# brain.net
KiCad netlist of a schematic drawn in Altium Designer
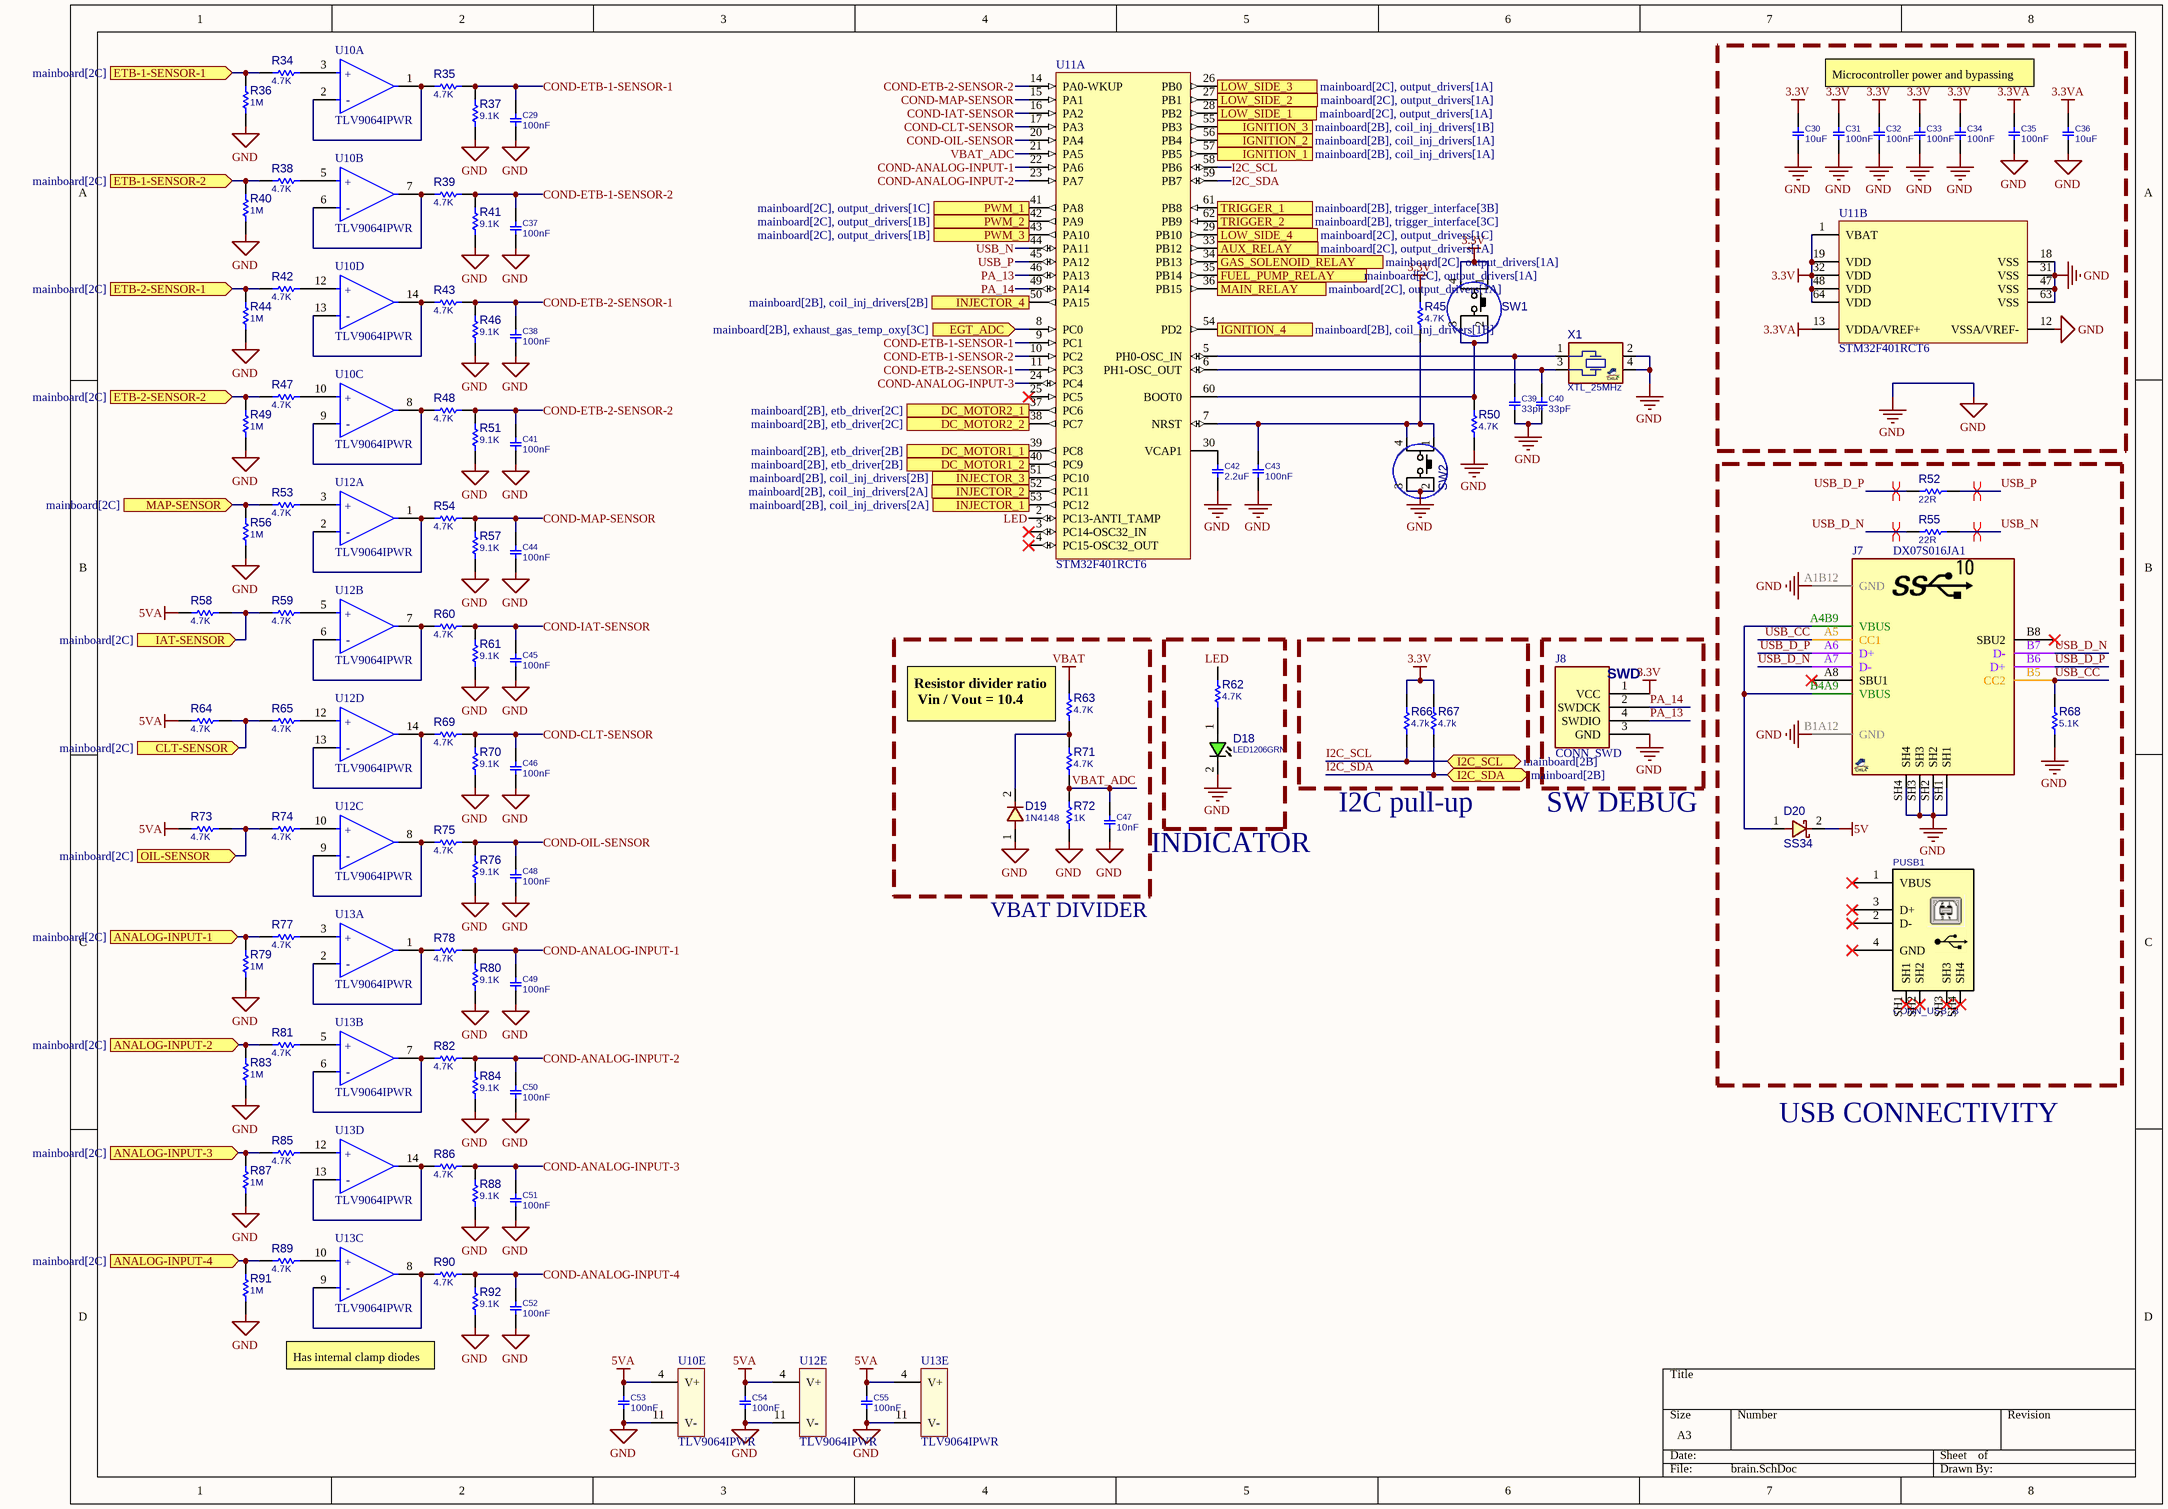
[diagram p0: brain.SchDoc]

(export (version "E")
  (design (tool "Eeschema 10.0.6"))
  (components
    (comp (ref "C29")
      (value "100nF")
      (footprint "C0805")
      (description "CAP, MLCC")
      (fields (field (name "MANF_P#") "MANF_PART#") (field (name "MANF") "Murata"))
      (libsource (lib "passive_smd") (part "CAP_SMD_MLCC"))
    )
    (comp (ref "C30")
      (value "10uF")
      (footprint "C0805")
      (description "CAP, MLCC")
      (fields (field (name "MANF_P#") "MANF_PART#") (field (name "MANF") "Murata"))
      (libsource (lib "passive_smd") (part "CAP_SMD_MLCC"))
    )
    (comp (ref "C31")
      (value "100nF")
      (footprint "C0805")
      (description "CAP, MLCC")
      (fields (field (name "MANF_P#") "MANF_PART#") (field (name "MANF") "Murata"))
      (libsource (lib "passive_smd") (part "CAP_SMD_MLCC"))
    )
    (comp (ref "C32")
      (value "100nF")
      (footprint "C0805")
      (description "CAP, MLCC")
      (fields (field (name "MANF_P#") "MANF_PART#") (field (name "MANF") "Murata"))
      (libsource (lib "passive_smd") (part "CAP_SMD_MLCC"))
    )
    (comp (ref "C33")
      (value "100nF")
      (footprint "C0805")
      (description "CAP, MLCC")
      (fields (field (name "MANF_P#") "MANF_PART#") (field (name "MANF") "Murata"))
      (libsource (lib "passive_smd") (part "CAP_SMD_MLCC"))
    )
    (comp (ref "C34")
      (value "100nF")
      (footprint "C0805")
      (description "CAP, MLCC")
      (fields (field (name "MANF_P#") "MANF_PART#") (field (name "MANF") "Murata"))
      (libsource (lib "passive_smd") (part "CAP_SMD_MLCC"))
    )
    (comp (ref "C35")
      (value "100nF")
      (footprint "C0805")
      (description "CAP, MLCC")
      (fields (field (name "MANF_P#") "MANF_PART#") (field (name "MANF") "Murata"))
      (libsource (lib "passive_smd") (part "CAP_SMD_MLCC"))
    )
    (comp (ref "C36")
      (value "10uF")
      (footprint "C0805")
      (description "CAP, MLCC")
      (fields (field (name "MANF_P#") "MANF_PART#") (field (name "MANF") "Murata"))
      (libsource (lib "passive_smd") (part "CAP_SMD_MLCC"))
    )
    (comp (ref "C37")
      (value "100nF")
      (footprint "C0805")
      (description "CAP, MLCC")
      (fields (field (name "MANF_P#") "MANF_PART#") (field (name "MANF") "Murata"))
      (libsource (lib "passive_smd") (part "CAP_SMD_MLCC"))
    )
    (comp (ref "C38")
      (value "100nF")
      (footprint "C0805")
      (description "CAP, MLCC")
      (fields (field (name "MANF_P#") "MANF_PART#") (field (name "MANF") "Murata"))
      (libsource (lib "passive_smd") (part "CAP_SMD_MLCC"))
    )
    (comp (ref "C39")
      (value "33pF")
      (footprint "C0805")
      (description "CAP, MLCC")
      (fields (field (name "MANF_P#") "MANF_PART#") (field (name "MANF") "Murata"))
      (libsource (lib "passive_smd") (part "CAP_SMD_MLCC"))
    )
    (comp (ref "C40")
      (value "33pF")
      (footprint "C0805")
      (description "CAP, MLCC")
      (fields (field (name "MANF_P#") "MANF_PART#") (field (name "MANF") "Murata"))
      (libsource (lib "passive_smd") (part "CAP_SMD_MLCC"))
    )
    (comp (ref "C41")
      (value "100nF")
      (footprint "C0805")
      (description "CAP, MLCC")
      (fields (field (name "MANF_P#") "MANF_PART#") (field (name "MANF") "Murata"))
      (libsource (lib "passive_smd") (part "CAP_SMD_MLCC"))
    )
    (comp (ref "C42")
      (value "2.2uF")
      (footprint "C0805")
      (description "CAP, MLCC")
      (fields (field (name "MANF_P#") "MANF_PART#") (field (name "MANF") "Murata"))
      (libsource (lib "passive_smd") (part "CAP_SMD_MLCC"))
    )
    (comp (ref "C43")
      (value "100nF")
      (footprint "C0805")
      (description "CAP, MLCC")
      (fields (field (name "MANF_P#") "MANF_PART#") (field (name "MANF") "Murata"))
      (libsource (lib "passive_smd") (part "CAP_SMD_MLCC"))
    )
    (comp (ref "C44")
      (value "100nF")
      (footprint "C0805")
      (description "CAP, MLCC")
      (fields (field (name "MANF_P#") "MANF_PART#") (field (name "MANF") "Murata"))
      (libsource (lib "passive_smd") (part "CAP_SMD_MLCC"))
    )
    (comp (ref "C45")
      (value "100nF")
      (footprint "C0805")
      (description "CAP, MLCC")
      (fields (field (name "MANF_P#") "MANF_PART#") (field (name "MANF") "Murata"))
      (libsource (lib "passive_smd") (part "CAP_SMD_MLCC"))
    )
    (comp (ref "C46")
      (value "100nF")
      (footprint "C0805")
      (description "CAP, MLCC")
      (fields (field (name "MANF_P#") "MANF_PART#") (field (name "MANF") "Murata"))
      (libsource (lib "passive_smd") (part "CAP_SMD_MLCC"))
    )
    (comp (ref "C47")
      (value "10nF")
      (footprint "C0805")
      (description "CAP, MLCC")
      (fields (field (name "MANF_P#") "MANF_PART#") (field (name "MANF") "Murata"))
      (libsource (lib "passive_smd") (part "CAP_SMD_MLCC"))
    )
    (comp (ref "C48")
      (value "100nF")
      (footprint "C0805")
      (description "CAP, MLCC")
      (fields (field (name "MANF_P#") "MANF_PART#") (field (name "MANF") "Murata"))
      (libsource (lib "passive_smd") (part "CAP_SMD_MLCC"))
    )
    (comp (ref "C49")
      (value "100nF")
      (footprint "C0805")
      (description "CAP, MLCC")
      (fields (field (name "MANF_P#") "MANF_PART#") (field (name "MANF") "Murata"))
      (libsource (lib "passive_smd") (part "CAP_SMD_MLCC"))
    )
    (comp (ref "C50")
      (value "100nF")
      (footprint "C0805")
      (description "CAP, MLCC")
      (fields (field (name "MANF_P#") "MANF_PART#") (field (name "MANF") "Murata"))
      (libsource (lib "passive_smd") (part "CAP_SMD_MLCC"))
    )
    (comp (ref "C51")
      (value "100nF")
      (footprint "C0805")
      (description "CAP, MLCC")
      (fields (field (name "MANF_P#") "MANF_PART#") (field (name "MANF") "Murata"))
      (libsource (lib "passive_smd") (part "CAP_SMD_MLCC"))
    )
    (comp (ref "C52")
      (value "100nF")
      (footprint "C0805")
      (description "CAP, MLCC")
      (fields (field (name "MANF_P#") "MANF_PART#") (field (name "MANF") "Murata"))
      (libsource (lib "passive_smd") (part "CAP_SMD_MLCC"))
    )
    (comp (ref "C53")
      (value "100nF")
      (footprint "C0805")
      (description "CAP, MLCC")
      (fields (field (name "MANF_P#") "MANF_PART#") (field (name "MANF") "Murata"))
      (libsource (lib "passive_smd") (part "CAP_SMD_MLCC"))
    )
    (comp (ref "C54")
      (value "100nF")
      (footprint "C0805")
      (description "CAP, MLCC")
      (fields (field (name "MANF_P#") "MANF_PART#") (field (name "MANF") "Murata"))
      (libsource (lib "passive_smd") (part "CAP_SMD_MLCC"))
    )
    (comp (ref "C55")
      (value "100nF")
      (footprint "C0805")
      (description "CAP, MLCC")
      (fields (field (name "MANF_P#") "MANF_PART#") (field (name "MANF") "Murata"))
      (libsource (lib "passive_smd") (part "CAP_SMD_MLCC"))
    )
    (comp (ref "D18")
      (value "LED1206GRN")
      (footprint "LED1206GRN")
      (description "LED, SMD, 1206, GREEN")
      (libsource (lib "led(diode)") (part "LED_SMD_1206_GRN"))
    )
    (comp (ref "D19")
      (value "1N4148")
      (footprint "D_SOD80")
      (description "DIODE, FAST SWTICHING, 0.3A, 0.5W")
      (fields (field (name "MANF") "MANF"))
      (libsource (lib "diode") (part "DIODE_SMD_1N4148_SOD80"))
    )
    (comp (ref "D20")
      (value "SS34")
      (footprint "D_SMB")
      (description "DIODE, SCHOTTKY, 20V, 3A")
      (fields (field (name "MANF") "VISHAY"))
      (libsource (lib "diode") (part "DIODE_SMD_SCHOTTKY_SS34"))
    )
    (comp (ref "J7")
      (value "DX07S016JA1")
      (footprint "USBC_SMD_16_DX07S016JA1")
      (description "CONN, USB, Type C, USB 2.0, Right-Angle, SMD")
      (fields (field (name "MANF") "JAE") (field (name "MANF_P#") "DX07S016JA1R1500"))
      (libsource (lib "conn_usbc") (part "CONN_USBC_SMD_16_DX07S016JA1"))
    )
    (comp (ref "J8")
      (value "CONN_SWD")
      (footprint "WF_4")
      (description "CONN, SWD, ST")
      (libsource (lib "conn_program") (part "CONN_SWD"))
    )
    (comp (ref "PUSB1")
      (value "CONN_USB_B")
      (footprint "USB_B_ST")
      (description "CONN, USB, B, STRAIGHT, THD")
      (libsource (lib "conn_usb") (part "CONN_USB_B_ST"))
    )
    (comp (ref "R34")
      (value "4.7K")
      (footprint "R0805")
      (description "RESISTOR, SMD")
      (libsource (lib "passive_smd") (part "RES_SMD"))
    )
    (comp (ref "R35")
      (value "4.7K")
      (footprint "R0805")
      (description "RESISTOR, SMD")
      (libsource (lib "passive_smd") (part "RES_SMD"))
    )
    (comp (ref "R36")
      (value "1M")
      (footprint "R0805")
      (description "RESISTOR, SMD")
      (libsource (lib "passive_smd") (part "RES_SMD"))
    )
    (comp (ref "R37")
      (value "9.1K")
      (footprint "R0805")
      (description "RESISTOR, SMD")
      (libsource (lib "passive_smd") (part "RES_SMD"))
    )
    (comp (ref "R38")
      (value "4.7K")
      (footprint "R0805")
      (description "RESISTOR, SMD")
      (libsource (lib "passive_smd") (part "RES_SMD"))
    )
    (comp (ref "R39")
      (value "4.7K")
      (footprint "R0805")
      (description "RESISTOR, SMD")
      (libsource (lib "passive_smd") (part "RES_SMD"))
    )
    (comp (ref "R40")
      (value "1M")
      (footprint "R0805")
      (description "RESISTOR, SMD")
      (libsource (lib "passive_smd") (part "RES_SMD"))
    )
    (comp (ref "R41")
      (value "9.1K")
      (footprint "R0805")
      (description "RESISTOR, SMD")
      (libsource (lib "passive_smd") (part "RES_SMD"))
    )
    (comp (ref "R42")
      (value "4.7K")
      (footprint "R0805")
      (description "RESISTOR, SMD")
      (libsource (lib "passive_smd") (part "RES_SMD"))
    )
    (comp (ref "R43")
      (value "4.7K")
      (footprint "R0805")
      (description "RESISTOR, SMD")
      (libsource (lib "passive_smd") (part "RES_SMD"))
    )
    (comp (ref "R44")
      (value "1M")
      (footprint "R0805")
      (description "RESISTOR, SMD")
      (libsource (lib "passive_smd") (part "RES_SMD"))
    )
    (comp (ref "R45")
      (value "4.7K")
      (footprint "R0805")
      (description "RESISTOR, SMD")
      (libsource (lib "passive_smd") (part "RES_SMD"))
    )
    (comp (ref "R46")
      (value "9.1K")
      (footprint "R0805")
      (description "RESISTOR, SMD")
      (libsource (lib "passive_smd") (part "RES_SMD"))
    )
    (comp (ref "R47")
      (value "4.7K")
      (footprint "R0805")
      (description "RESISTOR, SMD")
      (libsource (lib "passive_smd") (part "RES_SMD"))
    )
    (comp (ref "R48")
      (value "4.7K")
      (footprint "R0805")
      (description "RESISTOR, SMD")
      (libsource (lib "passive_smd") (part "RES_SMD"))
    )
    (comp (ref "R49")
      (value "1M")
      (footprint "R0805")
      (description "RESISTOR, SMD")
      (libsource (lib "passive_smd") (part "RES_SMD"))
    )
    (comp (ref "R50")
      (value "4.7K")
      (footprint "R0805")
      (description "RESISTOR, SMD")
      (libsource (lib "passive_smd") (part "RES_SMD"))
    )
    (comp (ref "R51")
      (value "9.1K")
      (footprint "R0805")
      (description "RESISTOR, SMD")
      (libsource (lib "passive_smd") (part "RES_SMD"))
    )
    (comp (ref "R52")
      (value "22R")
      (footprint "R0805")
      (description "RESISTOR, SMD")
      (libsource (lib "passive_smd") (part "RES_SMD_0805"))
    )
    (comp (ref "R53")
      (value "4.7K")
      (footprint "R0805")
      (description "RESISTOR, SMD")
      (libsource (lib "passive_smd") (part "RES_SMD"))
    )
    (comp (ref "R54")
      (value "4.7K")
      (footprint "R0805")
      (description "RESISTOR, SMD")
      (libsource (lib "passive_smd") (part "RES_SMD"))
    )
    (comp (ref "R55")
      (value "22R")
      (footprint "R0805")
      (description "RESISTOR, SMD")
      (libsource (lib "passive_smd") (part "RES_SMD_0805"))
    )
    (comp (ref "R56")
      (value "1M")
      (footprint "R0805")
      (description "RESISTOR, SMD")
      (libsource (lib "passive_smd") (part "RES_SMD"))
    )
    (comp (ref "R57")
      (value "9.1K")
      (footprint "R0805")
      (description "RESISTOR, SMD")
      (libsource (lib "passive_smd") (part "RES_SMD"))
    )
    (comp (ref "R58")
      (value "4.7K")
      (footprint "R0805")
      (description "RESISTOR, SMD")
      (libsource (lib "passive_smd") (part "RES_SMD"))
    )
    (comp (ref "R59")
      (value "4.7K")
      (footprint "R0805")
      (description "RESISTOR, SMD")
      (libsource (lib "passive_smd") (part "RES_SMD"))
    )
    (comp (ref "R60")
      (value "4.7K")
      (footprint "R0805")
      (description "RESISTOR, SMD")
      (libsource (lib "passive_smd") (part "RES_SMD"))
    )
    (comp (ref "R61")
      (value "9.1K")
      (footprint "R0805")
      (description "RESISTOR, SMD")
      (libsource (lib "passive_smd") (part "RES_SMD"))
    )
    (comp (ref "R62")
      (value "4.7K")
      (footprint "R0805")
      (description "RESISTOR, SMD")
      (libsource (lib "passive_smd") (part "RES_SMD"))
    )
    (comp (ref "R63")
      (value "4.7K")
      (footprint "R0805")
      (description "RESISTOR, SMD")
      (libsource (lib "passive_smd") (part "RES_SMD"))
    )
    (comp (ref "R64")
      (value "4.7K")
      (footprint "R0805")
      (description "RESISTOR, SMD")
      (libsource (lib "passive_smd") (part "RES_SMD"))
    )
    (comp (ref "R65")
      (value "4.7K")
      (footprint "R0805")
      (description "RESISTOR, SMD")
      (libsource (lib "passive_smd") (part "RES_SMD"))
    )
    (comp (ref "R66")
      (value "4.7k")
      (footprint "R0805")
      (description "RESISTOR, SMD")
      (libsource (lib "passive_smd") (part "RES_SMD"))
    )
    (comp (ref "R67")
      (value "4.7k")
      (footprint "R0805")
      (description "RESISTOR, SMD")
      (libsource (lib "passive_smd") (part "RES_SMD"))
    )
    (comp (ref "R68")
      (value "5.1K")
      (footprint "R0805")
      (description "RESISTOR, SMD")
      (libsource (lib "passive_smd") (part "RES_SMD_0805"))
    )
    (comp (ref "R69")
      (value "4.7K")
      (footprint "R0805")
      (description "RESISTOR, SMD")
      (libsource (lib "passive_smd") (part "RES_SMD"))
    )
    (comp (ref "R70")
      (value "9.1K")
      (footprint "R0805")
      (description "RESISTOR, SMD")
      (libsource (lib "passive_smd") (part "RES_SMD"))
    )
    (comp (ref "R71")
      (value "4.7K")
      (footprint "R0805")
      (description "RESISTOR, SMD")
      (libsource (lib "passive_smd") (part "RES_SMD"))
    )
    (comp (ref "R72")
      (value "1K")
      (footprint "R0805")
      (description "RESISTOR, SMD")
      (libsource (lib "passive_smd") (part "RES_SMD"))
    )
    (comp (ref "R73")
      (value "4.7K")
      (footprint "R0805")
      (description "RESISTOR, SMD")
      (libsource (lib "passive_smd") (part "RES_SMD"))
    )
    (comp (ref "R74")
      (value "4.7K")
      (footprint "R0805")
      (description "RESISTOR, SMD")
      (libsource (lib "passive_smd") (part "RES_SMD"))
    )
    (comp (ref "R75")
      (value "4.7K")
      (footprint "R0805")
      (description "RESISTOR, SMD")
      (libsource (lib "passive_smd") (part "RES_SMD"))
    )
    (comp (ref "R76")
      (value "9.1K")
      (footprint "R0805")
      (description "RESISTOR, SMD")
      (libsource (lib "passive_smd") (part "RES_SMD"))
    )
    (comp (ref "R77")
      (value "4.7K")
      (footprint "R0805")
      (description "RESISTOR, SMD")
      (libsource (lib "passive_smd") (part "RES_SMD"))
    )
    (comp (ref "R78")
      (value "4.7K")
      (footprint "R0805")
      (description "RESISTOR, SMD")
      (libsource (lib "passive_smd") (part "RES_SMD"))
    )
    (comp (ref "R79")
      (value "1M")
      (footprint "R0805")
      (description "RESISTOR, SMD")
      (libsource (lib "passive_smd") (part "RES_SMD"))
    )
    (comp (ref "R80")
      (value "9.1K")
      (footprint "R0805")
      (description "RESISTOR, SMD")
      (libsource (lib "passive_smd") (part "RES_SMD"))
    )
    (comp (ref "R81")
      (value "4.7K")
      (footprint "R0805")
      (description "RESISTOR, SMD")
      (libsource (lib "passive_smd") (part "RES_SMD"))
    )
    (comp (ref "R82")
      (value "4.7K")
      (footprint "R0805")
      (description "RESISTOR, SMD")
      (libsource (lib "passive_smd") (part "RES_SMD"))
    )
    (comp (ref "R83")
      (value "1M")
      (footprint "R0805")
      (description "RESISTOR, SMD")
      (libsource (lib "passive_smd") (part "RES_SMD"))
    )
    (comp (ref "R84")
      (value "9.1K")
      (footprint "R0805")
      (description "RESISTOR, SMD")
      (libsource (lib "passive_smd") (part "RES_SMD"))
    )
    (comp (ref "R85")
      (value "4.7K")
      (footprint "R0805")
      (description "RESISTOR, SMD")
      (libsource (lib "passive_smd") (part "RES_SMD"))
    )
    (comp (ref "R86")
      (value "4.7K")
      (footprint "R0805")
      (description "RESISTOR, SMD")
      (libsource (lib "passive_smd") (part "RES_SMD"))
    )
    (comp (ref "R87")
      (value "1M")
      (footprint "R0805")
      (description "RESISTOR, SMD")
      (libsource (lib "passive_smd") (part "RES_SMD"))
    )
    (comp (ref "R88")
      (value "9.1K")
      (footprint "R0805")
      (description "RESISTOR, SMD")
      (libsource (lib "passive_smd") (part "RES_SMD"))
    )
    (comp (ref "R89")
      (value "4.7K")
      (footprint "R0805")
      (description "RESISTOR, SMD")
      (libsource (lib "passive_smd") (part "RES_SMD"))
    )
    (comp (ref "R90")
      (value "4.7K")
      (footprint "R0805")
      (description "RESISTOR, SMD")
      (libsource (lib "passive_smd") (part "RES_SMD"))
    )
    (comp (ref "R91")
      (value "1M")
      (footprint "R0805")
      (description "RESISTOR, SMD")
      (libsource (lib "passive_smd") (part "RES_SMD"))
    )
    (comp (ref "R92")
      (value "9.1K")
      (footprint "R0805")
      (description "RESISTOR, SMD")
      (libsource (lib "passive_smd") (part "RES_SMD"))
    )
    (comp (ref "SW1")
      (value "PUSHBUTTON")
      (footprint "SWPBS_SPDT_5X5X1")
      (description "SWITCH, PUSH BUTTON, TACTILE, SMD, SPDT, 5X5MM")
      (fields (field (name "MANF") "CHINA") (field (name "MANF_P#") "PTS526SM15SMTR2LFS"))
      (libsource (lib "switch_tact_PUSHB") (part "SWPBS_SPDT_5X5PTS"))
    )
    (comp (ref "SW2")
      (value "PUSHBUTTON")
      (footprint "SWPBS_SPDT_5X5X1")
      (description "SWITCH, PUSH BUTTON, TACTILE, SMD, SPDT, 5X5MM")
      (fields (field (name "MANF") "CHINA") (field (name "MANF_P#") "PTS526SM15SMTR2LFS"))
      (libsource (lib "switch_tact_PUSHB") (part "SWPBS_SPDT_5X5PTS"))
    )
    (comp (ref "U10")
      (value "TLV9064IPWR")
      (footprint "TTSOP-14")
      (description "IC CMOS 4 CIRCUIT 14TSSOP")
      (libsource (lib "alib") (part "TLV9064"))
    )
    (comp (ref "U11")
      (value "STM32F401RCT6")
      (footprint "STM-LQFP64_L")
      (fields (field (name "MANUFACTURER") "STMicroelectronics"))
      (libsource (lib "Alib") (part "STM32F401RCT6"))
    )
    (comp (ref "U12")
      (value "TLV9064IPWR")
      (footprint "TTSOP-14")
      (description "IC CMOS 4 CIRCUIT 14TSSOP")
      (libsource (lib "alib") (part "TLV9064"))
    )
    (comp (ref "U13")
      (value "TLV9064IPWR")
      (footprint "TTSOP-14")
      (description "IC CMOS 4 CIRCUIT 14TSSOP")
      (libsource (lib "alib") (part "TLV9064"))
    )
    (comp (ref "X1")
      (value "XTL_25MHz")
      (footprint "XTL_4_3225")
      (description "CRYSTAL 25.00 MHZ 4pF, 10PPM")
      (fields (field (name "MANF") "ABRACON") (field (name "MANF_P#") "ABM8W-25.0000MHZ-4-D1X-T3"))
      (libsource (lib "crystal") (part "XTL_4_25MHZ_3225A_2"))
    )
  )
  (nets
    (net (code "1") (name "/ANALOG-INPUT-1") (class "Default")
      (node (ref "R77") (pin "2") (pinfunction "2_2") (pintype "passive"))
      (node (ref "R79") (pin "1") (pinfunction "1_1") (pintype "passive"))
    )
    (net (code "2") (name "/ANALOG-INPUT-2") (class "Default")
      (node (ref "R81") (pin "2") (pinfunction "2_2") (pintype "passive"))
      (node (ref "R83") (pin "1") (pinfunction "1_1") (pintype "passive"))
    )
    (net (code "3") (name "/ANALOG-INPUT-3") (class "Default")
      (node (ref "R85") (pin "2") (pinfunction "2_2") (pintype "passive"))
      (node (ref "R87") (pin "1") (pinfunction "1_1") (pintype "passive"))
    )
    (net (code "4") (name "/ANALOG-INPUT-4") (class "Default")
      (node (ref "R89") (pin "2") (pinfunction "2_2") (pintype "passive"))
      (node (ref "R91") (pin "1") (pinfunction "1_1") (pintype "passive"))
    )
    (net (code "5") (name "/AUX_RELAY") (class "Default")
      (node (ref "U11") (pin "33") (pinfunction "PB12_33") (pintype "output"))
    )
    (net (code "6") (name "/CLT-SENSOR") (class "Default")
      (node (ref "R64") (pin "1") (pinfunction "1_1") (pintype "passive"))
      (node (ref "R65") (pin "2") (pinfunction "2_2") (pintype "passive"))
    )
    (net (code "7") (name "/COND-ANALOG-INPUT-1") (class "Default")
      (node (ref "C49") (pin "2") (pinfunction "2_2") (pintype "passive"))
      (node (ref "R78") (pin "1") (pinfunction "1_1") (pintype "passive"))
      (node (ref "R80") (pin "1") (pinfunction "1_1") (pintype "passive"))
      (node (ref "U11") (pin "22") (pinfunction "PA6_22") (pintype "input"))
    )
    (net (code "8") (name "/COND-ANALOG-INPUT-2") (class "Default")
      (node (ref "C50") (pin "2") (pinfunction "2_2") (pintype "passive"))
      (node (ref "R82") (pin "1") (pinfunction "1_1") (pintype "passive"))
      (node (ref "R84") (pin "1") (pinfunction "1_1") (pintype "passive"))
      (node (ref "U11") (pin "23") (pinfunction "PA7_23") (pintype "input"))
    )
    (net (code "9") (name "/COND-ANALOG-INPUT-3") (class "Default")
      (node (ref "C51") (pin "2") (pinfunction "2_2") (pintype "passive"))
      (node (ref "R86") (pin "1") (pinfunction "1_1") (pintype "passive"))
      (node (ref "R88") (pin "1") (pinfunction "1_1") (pintype "passive"))
      (node (ref "U11") (pin "24") (pinfunction "PC4_24") (pintype "bidirectional"))
    )
    (net (code "10") (name "/COND-ANALOG-INPUT-4") (class "Default")
      (node (ref "C52") (pin "2") (pinfunction "2_2") (pintype "passive"))
      (node (ref "R90") (pin "1") (pinfunction "1_1") (pintype "passive"))
      (node (ref "R92") (pin "1") (pinfunction "1_1") (pintype "passive"))
    )
    (net (code "11") (name "/COND-CLT-SENSOR") (class "Default")
      (node (ref "C46") (pin "2") (pinfunction "2_2") (pintype "passive"))
      (node (ref "R69") (pin "1") (pinfunction "1_1") (pintype "passive"))
      (node (ref "R70") (pin "1") (pinfunction "1_1") (pintype "passive"))
      (node (ref "U11") (pin "17") (pinfunction "PA3_17") (pintype "input"))
    )
    (net (code "12") (name "/COND-ETB-1-SENSOR-1") (class "Default")
      (node (ref "C29") (pin "2") (pinfunction "2_2") (pintype "passive"))
      (node (ref "R35") (pin "1") (pinfunction "1_1") (pintype "passive"))
      (node (ref "R37") (pin "1") (pinfunction "1_1") (pintype "passive"))
      (node (ref "U11") (pin "9") (pinfunction "PC1_9") (pintype "input"))
    )
    (net (code "13") (name "/COND-ETB-1-SENSOR-2") (class "Default")
      (node (ref "C37") (pin "2") (pinfunction "2_2") (pintype "passive"))
      (node (ref "R39") (pin "1") (pinfunction "1_1") (pintype "passive"))
      (node (ref "R41") (pin "1") (pinfunction "1_1") (pintype "passive"))
      (node (ref "U11") (pin "10") (pinfunction "PC2_10") (pintype "input"))
    )
    (net (code "14") (name "/COND-ETB-2-SENSOR-1") (class "Default")
      (node (ref "C38") (pin "2") (pinfunction "2_2") (pintype "passive"))
      (node (ref "R43") (pin "1") (pinfunction "1_1") (pintype "passive"))
      (node (ref "R46") (pin "1") (pinfunction "1_1") (pintype "passive"))
      (node (ref "U11") (pin "11") (pinfunction "PC3_11") (pintype "input"))
    )
    (net (code "15") (name "/COND-ETB-2-SENSOR-2") (class "Default")
      (node (ref "C41") (pin "2") (pinfunction "2_2") (pintype "passive"))
      (node (ref "R48") (pin "1") (pinfunction "1_1") (pintype "passive"))
      (node (ref "R51") (pin "1") (pinfunction "1_1") (pintype "passive"))
      (node (ref "U11") (pin "14") (pinfunction "PA0-WKUP_14") (pintype "input"))
    )
    (net (code "16") (name "/COND-IAT-SENSOR") (class "Default")
      (node (ref "C45") (pin "2") (pinfunction "2_2") (pintype "passive"))
      (node (ref "R60") (pin "1") (pinfunction "1_1") (pintype "passive"))
      (node (ref "R61") (pin "1") (pinfunction "1_1") (pintype "passive"))
      (node (ref "U11") (pin "16") (pinfunction "PA2_16") (pintype "input"))
    )
    (net (code "17") (name "/COND-MAP-SENSOR") (class "Default")
      (node (ref "C44") (pin "2") (pinfunction "2_2") (pintype "passive"))
      (node (ref "R54") (pin "1") (pinfunction "1_1") (pintype "passive"))
      (node (ref "R57") (pin "1") (pinfunction "1_1") (pintype "passive"))
      (node (ref "U11") (pin "15") (pinfunction "PA1_15") (pintype "input"))
    )
    (net (code "18") (name "/COND-OIL-SENSOR") (class "Default")
      (node (ref "C48") (pin "2") (pinfunction "2_2") (pintype "passive"))
      (node (ref "R75") (pin "1") (pinfunction "1_1") (pintype "passive"))
      (node (ref "R76") (pin "1") (pinfunction "1_1") (pintype "passive"))
      (node (ref "U11") (pin "20") (pinfunction "PA4_20") (pintype "input"))
    )
    (net (code "19") (name "/DC_MOTOR1_1") (class "Default")
      (node (ref "U11") (pin "39") (pinfunction "PC8_39") (pintype "output"))
    )
    (net (code "20") (name "/DC_MOTOR1_2") (class "Default")
      (node (ref "U11") (pin "40") (pinfunction "PC9_40") (pintype "output"))
    )
    (net (code "21") (name "/DC_MOTOR2_1") (class "Default")
      (node (ref "U11") (pin "37") (pinfunction "PC6_37") (pintype "output"))
    )
    (net (code "22") (name "/DC_MOTOR2_2") (class "Default")
      (node (ref "U11") (pin "38") (pinfunction "PC7_38") (pintype "output"))
    )
    (net (code "23") (name "/EGT_ADC") (class "Default")
      (node (ref "U11") (pin "8") (pinfunction "PC0_8") (pintype "input"))
    )
    (net (code "24") (name "/ETB-1-SENSOR-1") (class "Default")
      (node (ref "R34") (pin "2") (pinfunction "2_2") (pintype "passive"))
      (node (ref "R36") (pin "1") (pinfunction "1_1") (pintype "passive"))
    )
    (net (code "25") (name "/ETB-1-SENSOR-2") (class "Default")
      (node (ref "R38") (pin "2") (pinfunction "2_2") (pintype "passive"))
      (node (ref "R40") (pin "1") (pinfunction "1_1") (pintype "passive"))
    )
    (net (code "26") (name "/ETB-2-SENSOR-1") (class "Default")
      (node (ref "R42") (pin "2") (pinfunction "2_2") (pintype "passive"))
      (node (ref "R44") (pin "1") (pinfunction "1_1") (pintype "passive"))
    )
    (net (code "27") (name "/ETB-2-SENSOR-2") (class "Default")
      (node (ref "R47") (pin "2") (pinfunction "2_2") (pintype "passive"))
      (node (ref "R49") (pin "1") (pinfunction "1_1") (pintype "passive"))
    )
    (net (code "28") (name "/FUEL_PUMP_RELAY") (class "Default")
      (node (ref "U11") (pin "35") (pinfunction "PB14_35") (pintype "output"))
    )
    (net (code "29") (name "/GAS_SOLENOID_RELAY") (class "Default")
      (node (ref "U11") (pin "34") (pinfunction "PB13_34") (pintype "output"))
    )
    (net (code "30") (name "/I2C_SCL") (class "Default")
      (node (ref "R66") (pin "1") (pinfunction "1_1") (pintype "passive"))
      (node (ref "U11") (pin "58") (pinfunction "PB6_58") (pintype "bidirectional"))
    )
    (net (code "31") (name "/I2C_SDA") (class "Default")
      (node (ref "R67") (pin "1") (pinfunction "1_1") (pintype "passive"))
      (node (ref "U11") (pin "59") (pinfunction "PB7_59") (pintype "bidirectional"))
    )
    (net (code "32") (name "/IAT-SENSOR") (class "Default")
      (node (ref "R58") (pin "1") (pinfunction "1_1") (pintype "passive"))
      (node (ref "R59") (pin "2") (pinfunction "2_2") (pintype "passive"))
    )
    (net (code "33") (name "/IGNITION_1") (class "Default")
      (node (ref "U11") (pin "57") (pinfunction "PB5_57") (pintype "output"))
    )
    (net (code "34") (name "/IGNITION_2") (class "Default")
      (node (ref "U11") (pin "56") (pinfunction "PB4_56") (pintype "output"))
    )
    (net (code "35") (name "/IGNITION_3") (class "Default")
      (node (ref "U11") (pin "55") (pinfunction "PB3_55") (pintype "output"))
    )
    (net (code "36") (name "/IGNITION_4") (class "Default")
      (node (ref "U11") (pin "54") (pinfunction "PD2_54") (pintype "output"))
    )
    (net (code "37") (name "/INJECTOR_1") (class "Default")
      (node (ref "U11") (pin "53") (pinfunction "PC12_53") (pintype "output"))
    )
    (net (code "38") (name "/INJECTOR_2") (class "Default")
      (node (ref "U11") (pin "52") (pinfunction "PC11_52") (pintype "output"))
    )
    (net (code "39") (name "/INJECTOR_3") (class "Default")
      (node (ref "U11") (pin "51") (pinfunction "PC10_51") (pintype "output"))
    )
    (net (code "40") (name "/INJECTOR_4") (class "Default")
      (node (ref "U11") (pin "50") (pinfunction "PA15_50") (pintype "output"))
    )
    (net (code "41") (name "/LED") (class "Default")
      (node (ref "R62") (pin "2") (pinfunction "2_2") (pintype "passive"))
      (node (ref "U11") (pin "2") (pinfunction "PC13-ANTI_TAMP_2") (pintype "bidirectional"))
    )
    (net (code "42") (name "/LOW_SIDE_1") (class "Default")
      (node (ref "U11") (pin "28") (pinfunction "PB2_28") (pintype "output"))
    )
    (net (code "43") (name "/LOW_SIDE_2") (class "Default")
      (node (ref "U11") (pin "27") (pinfunction "PB1_27") (pintype "output"))
    )
    (net (code "44") (name "/LOW_SIDE_3") (class "Default")
      (node (ref "U11") (pin "26") (pinfunction "PB0_26") (pintype "output"))
    )
    (net (code "45") (name "/LOW_SIDE_4") (class "Default")
      (node (ref "U11") (pin "29") (pinfunction "PB10_29") (pintype "output"))
    )
    (net (code "46") (name "/MAIN_RELAY") (class "Default")
      (node (ref "U11") (pin "36") (pinfunction "PB15_36") (pintype "output"))
    )
    (net (code "47") (name "/MAP-SENSOR") (class "Default")
      (node (ref "R53") (pin "2") (pinfunction "2_2") (pintype "passive"))
      (node (ref "R56") (pin "1") (pinfunction "1_1") (pintype "passive"))
    )
    (net (code "48") (name "/OIL-SENSOR") (class "Default")
      (node (ref "R73") (pin "1") (pinfunction "1_1") (pintype "passive"))
      (node (ref "R74") (pin "2") (pinfunction "2_2") (pintype "passive"))
    )
    (net (code "49") (name "/PA_13") (class "Default")
      (node (ref "J8") (pin "4") (pinfunction "SWDIO_4") (pintype "passive"))
      (node (ref "U11") (pin "46") (pinfunction "PA13_46") (pintype "bidirectional"))
    )
    (net (code "50") (name "/PA_14") (class "Default")
      (node (ref "J8") (pin "2") (pinfunction "SWDCK_2") (pintype "passive"))
      (node (ref "U11") (pin "49") (pinfunction "PA14_49") (pintype "bidirectional"))
    )
    (net (code "51") (name "/PWM_1") (class "Default")
      (node (ref "U11") (pin "41") (pinfunction "PA8_41") (pintype "output"))
    )
    (net (code "52") (name "/PWM_2") (class "Default")
      (node (ref "U11") (pin "42") (pinfunction "PA9_42") (pintype "output"))
    )
    (net (code "53") (name "/PWM_3") (class "Default")
      (node (ref "U11") (pin "43") (pinfunction "PA10_43") (pintype "output"))
    )
    (net (code "54") (name "/TRIGGER_1") (class "Default")
      (node (ref "U11") (pin "61") (pinfunction "PB8_61") (pintype "input"))
    )
    (net (code "55") (name "/TRIGGER_2") (class "Default")
      (node (ref "U11") (pin "62") (pinfunction "PB9_62") (pintype "input"))
    )
    (net (code "56") (name "/USB_CC") (class "Default")
      (node (ref "J7") (pin "A5") (pinfunction "CC1_A5") (pintype "passive"))
      (node (ref "J7") (pin "B5") (pinfunction "CC2_B5") (pintype "passive"))
      (node (ref "R68") (pin "2") (pinfunction "2_2") (pintype "passive"))
    )
    (net (code "57") (name "/USB_D_N") (class "Default")
      (node (ref "J7") (pin "A7") (pinfunction "D-_A7") (pintype "passive"))
      (node (ref "J7") (pin "B7") (pinfunction "D-_B7") (pintype "passive"))
      (node (ref "R55") (pin "2") (pinfunction "2_2") (pintype "passive"))
    )
    (net (code "58") (name "/USB_D_P") (class "Default")
      (node (ref "J7") (pin "A6") (pinfunction "D+_A6") (pintype "passive"))
      (node (ref "J7") (pin "B6") (pinfunction "D+_B6") (pintype "passive"))
      (node (ref "R52") (pin "2") (pinfunction "2_2") (pintype "passive"))
    )
    (net (code "59") (name "/USB_N") (class "Default")
      (node (ref "R55") (pin "1") (pinfunction "1_1") (pintype "passive"))
      (node (ref "U11") (pin "44") (pinfunction "PA11_44") (pintype "bidirectional"))
    )
    (net (code "60") (name "/USB_P") (class "Default")
      (node (ref "R52") (pin "1") (pinfunction "1_1") (pintype "passive"))
      (node (ref "U11") (pin "45") (pinfunction "PA12_45") (pintype "bidirectional"))
    )
    (net (code "61") (name "/VBAT_ADC") (class "Default")
      (node (ref "C47") (pin "2") (pinfunction "2_2") (pintype "passive"))
      (node (ref "R71") (pin "1") (pinfunction "1_1") (pintype "passive"))
      (node (ref "R72") (pin "2") (pinfunction "2_2") (pintype "passive"))
      (node (ref "U11") (pin "21") (pinfunction "PA5_21") (pintype "input"))
    )
    (net (code "62") (name "3.3V") (class "Default")
      (node (ref "C30") (pin "2") (pinfunction "2_2") (pintype "passive"))
      (node (ref "C31") (pin "2") (pinfunction "2_2") (pintype "passive"))
      (node (ref "C32") (pin "2") (pinfunction "2_2") (pintype "passive"))
      (node (ref "C33") (pin "2") (pinfunction "2_2") (pintype "passive"))
      (node (ref "C34") (pin "2") (pinfunction "2_2") (pintype "passive"))
      (node (ref "J8") (pin "1") (pinfunction "VCC_1") (pintype "passive"))
      (node (ref "R45") (pin "2") (pinfunction "2_2") (pintype "passive"))
      (node (ref "R66") (pin "2") (pinfunction "2_2") (pintype "passive"))
      (node (ref "R67") (pin "2") (pinfunction "2_2") (pintype "passive"))
      (node (ref "SW1") (pin "1") (pinfunction "P1_1") (pintype "passive"))
      (node (ref "SW1") (pin "4") (pinfunction "P2_4") (pintype "passive"))
      (node (ref "U11") (pin "1") (pinfunction "VBAT_1") (pintype "power_in"))
      (node (ref "U11") (pin "19") (pinfunction "VDD_19") (pintype "power_in"))
      (node (ref "U11") (pin "32") (pinfunction "VDD_32") (pintype "power_in"))
      (node (ref "U11") (pin "48") (pinfunction "VDD_48") (pintype "power_in"))
      (node (ref "U11") (pin "64") (pinfunction "VDD_64") (pintype "power_in"))
    )
    (net (code "63") (name "3.3VA") (class "Default")
      (node (ref "C35") (pin "2") (pinfunction "2_2") (pintype "passive"))
      (node (ref "C36") (pin "2") (pinfunction "2_2") (pintype "passive"))
      (node (ref "U11") (pin "13") (pinfunction "VDDA/VREF+_13") (pintype "power_in"))
    )
    (net (code "64") (name "5V") (class "Default")
      (node (ref "D20") (pin "2") (pinfunction "2_2") (pintype "passive"))
    )
    (net (code "65") (name "5VA") (class "Default")
      (node (ref "C53") (pin "2") (pinfunction "2_2") (pintype "passive"))
      (node (ref "C54") (pin "2") (pinfunction "2_2") (pintype "passive"))
      (node (ref "C55") (pin "2") (pinfunction "2_2") (pintype "passive"))
      (node (ref "R58") (pin "2") (pinfunction "2_2") (pintype "passive"))
      (node (ref "R64") (pin "2") (pinfunction "2_2") (pintype "passive"))
      (node (ref "R73") (pin "2") (pinfunction "2_2") (pintype "passive"))
      (node (ref "U10") (pin "4") (pinfunction "V+_4") (pintype "power_in"))
      (node (ref "U12") (pin "4") (pinfunction "V+_4") (pintype "power_in"))
      (node (ref "U13") (pin "4") (pinfunction "V+_4") (pintype "power_in"))
    )
    (net (code "66") (name "GND") (class "Default")
      (node (ref "C29") (pin "1") (pinfunction "1_1") (pintype "passive"))
      (node (ref "C30") (pin "1") (pinfunction "1_1") (pintype "passive"))
      (node (ref "C31") (pin "1") (pinfunction "1_1") (pintype "passive"))
      (node (ref "C32") (pin "1") (pinfunction "1_1") (pintype "passive"))
      (node (ref "C33") (pin "1") (pinfunction "1_1") (pintype "passive"))
      (node (ref "C34") (pin "1") (pinfunction "1_1") (pintype "passive"))
      (node (ref "C35") (pin "1") (pinfunction "1_1") (pintype "passive"))
      (node (ref "C36") (pin "1") (pinfunction "1_1") (pintype "passive"))
      (node (ref "C37") (pin "1") (pinfunction "1_1") (pintype "passive"))
      (node (ref "C38") (pin "1") (pinfunction "1_1") (pintype "passive"))
      (node (ref "C39") (pin "1") (pinfunction "1_1") (pintype "passive"))
      (node (ref "C40") (pin "1") (pinfunction "1_1") (pintype "passive"))
      (node (ref "C41") (pin "1") (pinfunction "1_1") (pintype "passive"))
      (node (ref "C42") (pin "1") (pinfunction "1_1") (pintype "passive"))
      (node (ref "C43") (pin "1") (pinfunction "1_1") (pintype "passive"))
      (node (ref "C44") (pin "1") (pinfunction "1_1") (pintype "passive"))
      (node (ref "C45") (pin "1") (pinfunction "1_1") (pintype "passive"))
      (node (ref "C46") (pin "1") (pinfunction "1_1") (pintype "passive"))
      (node (ref "C47") (pin "1") (pinfunction "1_1") (pintype "passive"))
      (node (ref "C48") (pin "1") (pinfunction "1_1") (pintype "passive"))
      (node (ref "C49") (pin "1") (pinfunction "1_1") (pintype "passive"))
      (node (ref "C50") (pin "1") (pinfunction "1_1") (pintype "passive"))
      (node (ref "C51") (pin "1") (pinfunction "1_1") (pintype "passive"))
      (node (ref "C52") (pin "1") (pinfunction "1_1") (pintype "passive"))
      (node (ref "C53") (pin "1") (pinfunction "1_1") (pintype "passive"))
      (node (ref "C54") (pin "1") (pinfunction "1_1") (pintype "passive"))
      (node (ref "C55") (pin "1") (pinfunction "1_1") (pintype "passive"))
      (node (ref "D18") (pin "2") (pinfunction "CATHODE_2") (pintype "passive"))
      (node (ref "D19") (pin "1") (pinfunction "1_1") (pintype "passive"))
      (node (ref "J7") (pin "A1B12") (pinfunction "GND_A1B12") (pintype "passive"))
      (node (ref "J7") (pin "B1A12") (pinfunction "GND_B1A12") (pintype "passive"))
      (node (ref "J7") (pin "SH1") (pinfunction "SH1_SH1") (pintype "passive"))
      (node (ref "J7") (pin "SH2") (pinfunction "SH2_SH2") (pintype "passive"))
      (node (ref "J7") (pin "SH3") (pinfunction "SH3_SH3") (pintype "passive"))
      (node (ref "J7") (pin "SH4") (pinfunction "SH4_SH4") (pintype "passive"))
      (node (ref "J8") (pin "3") (pinfunction "GND_3") (pintype "passive"))
      (node (ref "R36") (pin "2") (pinfunction "2_2") (pintype "passive"))
      (node (ref "R37") (pin "2") (pinfunction "2_2") (pintype "passive"))
      (node (ref "R40") (pin "2") (pinfunction "2_2") (pintype "passive"))
      (node (ref "R41") (pin "2") (pinfunction "2_2") (pintype "passive"))
      (node (ref "R44") (pin "2") (pinfunction "2_2") (pintype "passive"))
      (node (ref "R46") (pin "2") (pinfunction "2_2") (pintype "passive"))
      (node (ref "R49") (pin "2") (pinfunction "2_2") (pintype "passive"))
      (node (ref "R50") (pin "1") (pinfunction "1_1") (pintype "passive"))
      (node (ref "R51") (pin "2") (pinfunction "2_2") (pintype "passive"))
      (node (ref "R56") (pin "2") (pinfunction "2_2") (pintype "passive"))
      (node (ref "R57") (pin "2") (pinfunction "2_2") (pintype "passive"))
      (node (ref "R61") (pin "2") (pinfunction "2_2") (pintype "passive"))
      (node (ref "R68") (pin "1") (pinfunction "1_1") (pintype "passive"))
      (node (ref "R70") (pin "2") (pinfunction "2_2") (pintype "passive"))
      (node (ref "R72") (pin "1") (pinfunction "1_1") (pintype "passive"))
      (node (ref "R76") (pin "2") (pinfunction "2_2") (pintype "passive"))
      (node (ref "R79") (pin "2") (pinfunction "2_2") (pintype "passive"))
      (node (ref "R80") (pin "2") (pinfunction "2_2") (pintype "passive"))
      (node (ref "R83") (pin "2") (pinfunction "2_2") (pintype "passive"))
      (node (ref "R84") (pin "2") (pinfunction "2_2") (pintype "passive"))
      (node (ref "R87") (pin "2") (pinfunction "2_2") (pintype "passive"))
      (node (ref "R88") (pin "2") (pinfunction "2_2") (pintype "passive"))
      (node (ref "R91") (pin "2") (pinfunction "2_2") (pintype "passive"))
      (node (ref "R92") (pin "2") (pinfunction "2_2") (pintype "passive"))
      (node (ref "SW2") (pin "2") (pinfunction "P3_2") (pintype "passive"))
      (node (ref "SW2") (pin "3") (pinfunction "P4_3") (pintype "passive"))
      (node (ref "U10") (pin "11") (pinfunction "V-_11") (pintype "power_in"))
      (node (ref "U11") (pin "12") (pinfunction "VSSA/VREF-_12") (pintype "power_in"))
      (node (ref "U11") (pin "18") (pinfunction "VSS_18") (pintype "power_in"))
      (node (ref "U11") (pin "31") (pinfunction "VSS_31") (pintype "power_in"))
      (node (ref "U11") (pin "47") (pinfunction "VSS_47") (pintype "power_in"))
      (node (ref "U11") (pin "63") (pinfunction "VSS_63") (pintype "power_in"))
      (node (ref "U12") (pin "11") (pinfunction "V-_11") (pintype "power_in"))
      (node (ref "U13") (pin "11") (pinfunction "V-_11") (pintype "power_in"))
      (node (ref "X1") (pin "2") (pinfunction "2_2") (pintype "passive"))
      (node (ref "X1") (pin "4") (pinfunction "4_4") (pintype "passive"))
    )
    (net (code "67") (name "Net-(D18-ANODE)") (class "Default")
      (node (ref "D18") (pin "1") (pinfunction "ANODE_1") (pintype "passive"))
      (node (ref "R62") (pin "1") (pinfunction "1_1") (pintype "passive"))
    )
    (net (code "68") (name "Net-(D19-Pad2)") (class "Default")
      (node (ref "D19") (pin "2") (pinfunction "2_2") (pintype "passive"))
      (node (ref "R63") (pin "1") (pinfunction "1_1") (pintype "passive"))
      (node (ref "R71") (pin "2") (pinfunction "2_2") (pintype "passive"))
    )
    (net (code "69") (name "Net-(D20-Pad1)") (class "Default")
      (node (ref "D20") (pin "1") (pinfunction "1_1") (pintype "passive"))
      (node (ref "J7") (pin "A4B9") (pinfunction "VBUS_A4B9") (pintype "passive"))
      (node (ref "J7") (pin "B4A9") (pinfunction "VBUS_B4A9") (pintype "passive"))
    )
    (net (code "70") (name "Net-(SW1-P3)") (class "Default")
      (node (ref "R50") (pin "2") (pinfunction "2_2") (pintype "passive"))
      (node (ref "SW1") (pin "2") (pinfunction "P3_2") (pintype "passive"))
      (node (ref "SW1") (pin "3") (pinfunction "P4_3") (pintype "passive"))
      (node (ref "U11") (pin "60") (pinfunction "BOOT0_60") (pintype "power_in"))
    )
    (net (code "71") (name "Net-(SW2-P1)") (class "Default")
      (node (ref "C43") (pin "2") (pinfunction "2_2") (pintype "passive"))
      (node (ref "R45") (pin "1") (pinfunction "1_1") (pintype "passive"))
      (node (ref "SW2") (pin "1") (pinfunction "P1_1") (pintype "passive"))
      (node (ref "SW2") (pin "4") (pinfunction "P2_4") (pintype "passive"))
      (node (ref "U11") (pin "7") (pinfunction "NRST_7") (pintype "bidirectional"))
    )
    (net (code "72") (name "Net-(U10A-IN1+)") (class "Default")
      (node (ref "R34") (pin "1") (pinfunction "1_1") (pintype "passive"))
      (node (ref "U10") (pin "3") (pinfunction "IN1+_3") (pintype "passive"))
    )
    (net (code "73") (name "Net-(U10A-IN1-)") (class "Default")
      (node (ref "R35") (pin "2") (pinfunction "2_2") (pintype "passive"))
      (node (ref "U10") (pin "1") (pinfunction "OUT1_1") (pintype "passive"))
      (node (ref "U10") (pin "2") (pinfunction "IN1-_2") (pintype "passive"))
    )
    (net (code "74") (name "Net-(U10B-IN2+)") (class "Default")
      (node (ref "R38") (pin "1") (pinfunction "1_1") (pintype "passive"))
      (node (ref "U10") (pin "5") (pinfunction "IN2+_5") (pintype "passive"))
    )
    (net (code "75") (name "Net-(U10B-IN2-)") (class "Default")
      (node (ref "R39") (pin "2") (pinfunction "2_2") (pintype "passive"))
      (node (ref "U10") (pin "6") (pinfunction "IN2-_6") (pintype "passive"))
      (node (ref "U10") (pin "7") (pinfunction "OUT2_7") (pintype "passive"))
    )
    (net (code "76") (name "Net-(U10C-IN3+)") (class "Default")
      (node (ref "R47") (pin "1") (pinfunction "1_1") (pintype "passive"))
      (node (ref "U10") (pin "10") (pinfunction "IN3+_10") (pintype "passive"))
    )
    (net (code "77") (name "Net-(U10C-IN3-)") (class "Default")
      (node (ref "R48") (pin "2") (pinfunction "2_2") (pintype "passive"))
      (node (ref "U10") (pin "8") (pinfunction "OUT3_8") (pintype "passive"))
      (node (ref "U10") (pin "9") (pinfunction "IN3-_9") (pintype "passive"))
    )
    (net (code "78") (name "Net-(U10D-IN4+)") (class "Default")
      (node (ref "R42") (pin "1") (pinfunction "1_1") (pintype "passive"))
      (node (ref "U10") (pin "12") (pinfunction "IN4+_12") (pintype "passive"))
    )
    (net (code "79") (name "Net-(U10D-IN4-)") (class "Default")
      (node (ref "R43") (pin "2") (pinfunction "2_2") (pintype "passive"))
      (node (ref "U10") (pin "13") (pinfunction "IN4-_13") (pintype "passive"))
      (node (ref "U10") (pin "14") (pinfunction "OUT4_14") (pintype "passive"))
    )
    (net (code "80") (name "Net-(U11A-PH0-OSC_IN)") (class "Default")
      (node (ref "C39") (pin "2") (pinfunction "2_2") (pintype "passive"))
      (node (ref "U11") (pin "5") (pinfunction "PH0-OSC_IN_5") (pintype "bidirectional"))
      (node (ref "X1") (pin "1") (pinfunction "1_1") (pintype "passive"))
    )
    (net (code "81") (name "Net-(U11A-PH1-OSC_OUT)") (class "Default")
      (node (ref "C40") (pin "2") (pinfunction "2_2") (pintype "passive"))
      (node (ref "U11") (pin "6") (pinfunction "PH1-OSC_OUT_6") (pintype "bidirectional"))
      (node (ref "X1") (pin "3") (pinfunction "2_3") (pintype "passive"))
    )
    (net (code "82") (name "Net-(U11A-VCAP1)") (class "Default")
      (node (ref "C42") (pin "2") (pinfunction "2_2") (pintype "passive"))
      (node (ref "U11") (pin "30") (pinfunction "VCAP1_30") (pintype "power_in"))
    )
    (net (code "83") (name "Net-(U12A-IN1+)") (class "Default")
      (node (ref "R53") (pin "1") (pinfunction "1_1") (pintype "passive"))
      (node (ref "U12") (pin "3") (pinfunction "IN1+_3") (pintype "passive"))
    )
    (net (code "84") (name "Net-(U12A-IN1-)") (class "Default")
      (node (ref "R54") (pin "2") (pinfunction "2_2") (pintype "passive"))
      (node (ref "U12") (pin "1") (pinfunction "OUT1_1") (pintype "passive"))
      (node (ref "U12") (pin "2") (pinfunction "IN1-_2") (pintype "passive"))
    )
    (net (code "85") (name "Net-(U12B-IN2+)") (class "Default")
      (node (ref "R59") (pin "1") (pinfunction "1_1") (pintype "passive"))
      (node (ref "U12") (pin "5") (pinfunction "IN2+_5") (pintype "passive"))
    )
    (net (code "86") (name "Net-(U12B-IN2-)") (class "Default")
      (node (ref "R60") (pin "2") (pinfunction "2_2") (pintype "passive"))
      (node (ref "U12") (pin "6") (pinfunction "IN2-_6") (pintype "passive"))
      (node (ref "U12") (pin "7") (pinfunction "OUT2_7") (pintype "passive"))
    )
    (net (code "87") (name "Net-(U12C-IN3+)") (class "Default")
      (node (ref "R74") (pin "1") (pinfunction "1_1") (pintype "passive"))
      (node (ref "U12") (pin "10") (pinfunction "IN3+_10") (pintype "passive"))
    )
    (net (code "88") (name "Net-(U12C-IN3-)") (class "Default")
      (node (ref "R75") (pin "2") (pinfunction "2_2") (pintype "passive"))
      (node (ref "U12") (pin "8") (pinfunction "OUT3_8") (pintype "passive"))
      (node (ref "U12") (pin "9") (pinfunction "IN3-_9") (pintype "passive"))
    )
    (net (code "89") (name "Net-(U12D-IN4+)") (class "Default")
      (node (ref "R65") (pin "1") (pinfunction "1_1") (pintype "passive"))
      (node (ref "U12") (pin "12") (pinfunction "IN4+_12") (pintype "passive"))
    )
    (net (code "90") (name "Net-(U12D-IN4-)") (class "Default")
      (node (ref "R69") (pin "2") (pinfunction "2_2") (pintype "passive"))
      (node (ref "U12") (pin "13") (pinfunction "IN4-_13") (pintype "passive"))
      (node (ref "U12") (pin "14") (pinfunction "OUT4_14") (pintype "passive"))
    )
    (net (code "91") (name "Net-(U13A-IN1+)") (class "Default")
      (node (ref "R77") (pin "1") (pinfunction "1_1") (pintype "passive"))
      (node (ref "U13") (pin "3") (pinfunction "IN1+_3") (pintype "passive"))
    )
    (net (code "92") (name "Net-(U13A-IN1-)") (class "Default")
      (node (ref "R78") (pin "2") (pinfunction "2_2") (pintype "passive"))
      (node (ref "U13") (pin "1") (pinfunction "OUT1_1") (pintype "passive"))
      (node (ref "U13") (pin "2") (pinfunction "IN1-_2") (pintype "passive"))
    )
    (net (code "93") (name "Net-(U13B-IN2+)") (class "Default")
      (node (ref "R81") (pin "1") (pinfunction "1_1") (pintype "passive"))
      (node (ref "U13") (pin "5") (pinfunction "IN2+_5") (pintype "passive"))
    )
    (net (code "94") (name "Net-(U13B-IN2-)") (class "Default")
      (node (ref "R82") (pin "2") (pinfunction "2_2") (pintype "passive"))
      (node (ref "U13") (pin "6") (pinfunction "IN2-_6") (pintype "passive"))
      (node (ref "U13") (pin "7") (pinfunction "OUT2_7") (pintype "passive"))
    )
    (net (code "95") (name "Net-(U13C-IN3+)") (class "Default")
      (node (ref "R89") (pin "1") (pinfunction "1_1") (pintype "passive"))
      (node (ref "U13") (pin "10") (pinfunction "IN3+_10") (pintype "passive"))
    )
    (net (code "96") (name "Net-(U13C-IN3-)") (class "Default")
      (node (ref "R90") (pin "2") (pinfunction "2_2") (pintype "passive"))
      (node (ref "U13") (pin "8") (pinfunction "OUT3_8") (pintype "passive"))
      (node (ref "U13") (pin "9") (pinfunction "IN3-_9") (pintype "passive"))
    )
    (net (code "97") (name "Net-(U13D-IN4+)") (class "Default")
      (node (ref "R85") (pin "1") (pinfunction "1_1") (pintype "passive"))
      (node (ref "U13") (pin "12") (pinfunction "IN4+_12") (pintype "passive"))
    )
    (net (code "98") (name "Net-(U13D-IN4-)") (class "Default")
      (node (ref "R86") (pin "2") (pinfunction "2_2") (pintype "passive"))
      (node (ref "U13") (pin "13") (pinfunction "IN4-_13") (pintype "passive"))
      (node (ref "U13") (pin "14") (pinfunction "OUT4_14") (pintype "passive"))
    )
    (net (code "99") (name "VBAT") (class "Default")
      (node (ref "R63") (pin "2") (pinfunction "2_2") (pintype "passive"))
    )
    (net (code "100") (name "unconnected-(J7-SBU1-PadA8)") (class "Default")
      (node (ref "J7") (pin "A8") (pinfunction "SBU1_A8") (pintype "passive+no_connect"))
    )
    (net (code "101") (name "unconnected-(J7-SBU2-PadB8)") (class "Default")
      (node (ref "J7") (pin "B8") (pinfunction "SBU2_B8") (pintype "passive+no_connect"))
    )
    (net (code "102") (name "unconnected-(PUSB1-D+-Pad3)") (class "Default")
      (node (ref "PUSB1") (pin "3") (pinfunction "D+_3") (pintype "passive+no_connect"))
    )
    (net (code "103") (name "unconnected-(PUSB1-D--Pad2)") (class "Default")
      (node (ref "PUSB1") (pin "2") (pinfunction "D-_2") (pintype "passive+no_connect"))
    )
    (net (code "104") (name "unconnected-(PUSB1-GND-Pad4)") (class "Default")
      (node (ref "PUSB1") (pin "4") (pinfunction "GND_4") (pintype "power_in+no_connect"))
    )
    (net (code "105") (name "unconnected-(PUSB1-PadSH1)") (class "Default")
      (node (ref "PUSB1") (pin "SH1") (pinfunction "SH1_SH1") (pintype "passive+no_connect"))
    )
    (net (code "106") (name "unconnected-(PUSB1-PadSH2)") (class "Default")
      (node (ref "PUSB1") (pin "SH2") (pinfunction "SH2_SH2") (pintype "passive+no_connect"))
    )
    (net (code "107") (name "unconnected-(PUSB1-PadSH3)") (class "Default")
      (node (ref "PUSB1") (pin "SH3") (pinfunction "SH3_SH3") (pintype "passive+no_connect"))
    )
    (net (code "108") (name "unconnected-(PUSB1-PadSH4)") (class "Default")
      (node (ref "PUSB1") (pin "SH4") (pinfunction "SH4_SH4") (pintype "passive+no_connect"))
    )
    (net (code "109") (name "unconnected-(PUSB1-VBUS-Pad1)") (class "Default")
      (node (ref "PUSB1") (pin "1") (pinfunction "VBUS_1") (pintype "power_in+no_connect"))
    )
    (net (code "110") (name "unconnected-(U11A-PC5-Pad25)") (class "Default")
      (node (ref "U11") (pin "25") (pinfunction "PC5_25") (pintype "input+no_connect"))
    )
    (net (code "111") (name "unconnected-(U11A-PC14-OSC32_IN-Pad3)") (class "Default")
      (node (ref "U11") (pin "3") (pinfunction "PC14-OSC32_IN_3") (pintype "bidirectional+no_connect"))
    )
    (net (code "112") (name "unconnected-(U11A-PC15-OSC32_OUT-Pad4)") (class "Default")
      (node (ref "U11") (pin "4") (pinfunction "PC15-OSC32_OUT_4") (pintype "bidirectional+no_connect"))
    )
  )
)
